# LO.net
KiCad netlist of a schematic drawn in Altium Designer
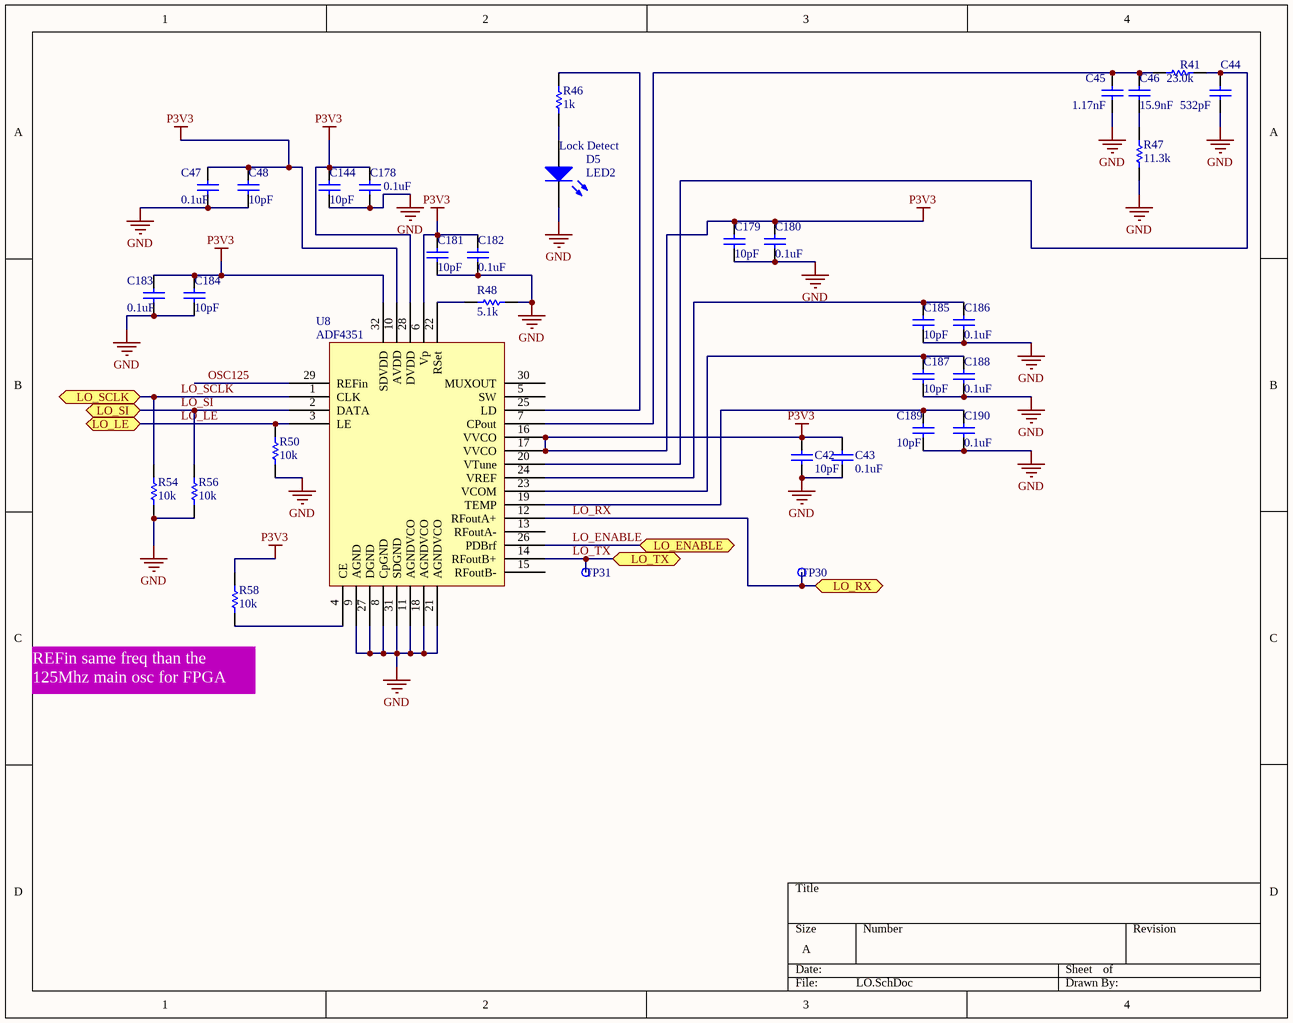
[diagram p0: LO.SchDoc]

(export (version "E")
  (design (tool "Eeschema 10.0.6"))
  (components
    (comp (ref "C42")
      (value "10pF")
      (footprint "0402")
      (description "Capacitor (Semiconductor SIM Model)")
      (fields (field (name "Comment") "Cap Semi") (field (name "PUBLISHER") "Altium Limited"))
      (libsource (lib "Miscellaneous Devices") (part "Cap Semi"))
    )
    (comp (ref "C43")
      (value "0.1uF")
      (footprint "0402")
      (description "Capacitor (Semiconductor SIM Model)")
      (fields (field (name "Comment") "Cap Semi") (field (name "PUBLISHER") "Altium Limited"))
      (libsource (lib "Miscellaneous Devices") (part "Cap Semi"))
    )
    (comp (ref "C44")
      (value "532pF")
      (footprint "0402")
      (description "Capacitor (Semiconductor SIM Model)")
      (fields (field (name "Comment") "Cap Semi") (field (name "PUBLISHER") "Altium Limited"))
      (libsource (lib "Miscellaneous Devices") (part "Cap Semi"))
    )
    (comp (ref "C45")
      (value "1.17nF")
      (footprint "0402")
      (description "Capacitor (Semiconductor SIM Model)")
      (fields (field (name "Comment") "Cap Semi") (field (name "PUBLISHER") "Altium Limited"))
      (libsource (lib "Miscellaneous Devices") (part "Cap Semi"))
    )
    (comp (ref "C46")
      (value "15.9nF")
      (footprint "0402")
      (description "Capacitor (Semiconductor SIM Model)")
      (fields (field (name "Comment") "Cap Semi") (field (name "PUBLISHER") "Altium Limited"))
      (libsource (lib "Miscellaneous Devices") (part "Cap Semi"))
    )
    (comp (ref "C47")
      (value "0.1uF")
      (footprint "0402")
      (description "Capacitor (Semiconductor SIM Model)")
      (fields (field (name "Comment") "Cap Semi") (field (name "PUBLISHER") "Altium Limited"))
      (libsource (lib "Miscellaneous Devices") (part "Cap Semi"))
    )
    (comp (ref "C48")
      (value "10pF")
      (footprint "0402")
      (description "Capacitor (Semiconductor SIM Model)")
      (fields (field (name "Comment") "Cap Semi") (field (name "PUBLISHER") "Altium Limited"))
      (libsource (lib "Miscellaneous Devices") (part "Cap Semi"))
    )
    (comp (ref "C144")
      (value "10pF")
      (footprint "0402")
      (description "Capacitor (Semiconductor SIM Model)")
      (fields (field (name "Comment") "Cap Semi") (field (name "PUBLISHER") "Altium Limited"))
      (libsource (lib "Miscellaneous Devices") (part "Cap Semi"))
    )
    (comp (ref "C178")
      (value "0.1uF")
      (footprint "0402")
      (description "Capacitor (Semiconductor SIM Model)")
      (fields (field (name "Comment") "Cap Semi") (field (name "PUBLISHER") "Altium Limited"))
      (libsource (lib "Miscellaneous Devices") (part "Cap Semi"))
    )
    (comp (ref "C179")
      (value "10pF")
      (footprint "0402")
      (description "Capacitor (Semiconductor SIM Model)")
      (fields (field (name "Comment") "Cap Semi") (field (name "PUBLISHER") "Altium Limited"))
      (libsource (lib "Miscellaneous Devices") (part "Cap Semi"))
    )
    (comp (ref "C180")
      (value "0.1uF")
      (footprint "0402")
      (description "Capacitor (Semiconductor SIM Model)")
      (fields (field (name "Comment") "Cap Semi") (field (name "PUBLISHER") "Altium Limited"))
      (libsource (lib "Miscellaneous Devices") (part "Cap Semi"))
    )
    (comp (ref "C181")
      (value "10pF")
      (footprint "0402")
      (description "Capacitor (Semiconductor SIM Model)")
      (fields (field (name "Comment") "Cap Semi") (field (name "PUBLISHER") "Altium Limited"))
      (libsource (lib "Miscellaneous Devices") (part "Cap Semi"))
    )
    (comp (ref "C182")
      (value "0.1uF")
      (footprint "0402")
      (description "Capacitor (Semiconductor SIM Model)")
      (fields (field (name "Comment") "Cap Semi") (field (name "PUBLISHER") "Altium Limited"))
      (libsource (lib "Miscellaneous Devices") (part "Cap Semi"))
    )
    (comp (ref "C183")
      (value "0.1uF")
      (footprint "0402")
      (description "Capacitor (Semiconductor SIM Model)")
      (fields (field (name "Comment") "Cap Semi") (field (name "PUBLISHER") "Altium Limited"))
      (libsource (lib "Miscellaneous Devices") (part "Cap Semi"))
    )
    (comp (ref "C184")
      (value "10pF")
      (footprint "0402")
      (description "Capacitor (Semiconductor SIM Model)")
      (fields (field (name "Comment") "Cap Semi") (field (name "PUBLISHER") "Altium Limited"))
      (libsource (lib "Miscellaneous Devices") (part "Cap Semi"))
    )
    (comp (ref "C185")
      (value "10pF")
      (footprint "0402")
      (description "Capacitor (Semiconductor SIM Model)")
      (fields (field (name "Comment") "Cap Semi") (field (name "PUBLISHER") "Altium Limited"))
      (libsource (lib "Miscellaneous Devices") (part "Cap Semi"))
    )
    (comp (ref "C186")
      (value "0.1uF")
      (footprint "0402")
      (description "Capacitor (Semiconductor SIM Model)")
      (fields (field (name "Comment") "Cap Semi") (field (name "PUBLISHER") "Altium Limited"))
      (libsource (lib "Miscellaneous Devices") (part "Cap Semi"))
    )
    (comp (ref "C187")
      (value "10pF")
      (footprint "0402")
      (description "Capacitor (Semiconductor SIM Model)")
      (fields (field (name "Comment") "Cap Semi") (field (name "PUBLISHER") "Altium Limited"))
      (libsource (lib "Miscellaneous Devices") (part "Cap Semi"))
    )
    (comp (ref "C188")
      (value "0.1uF")
      (footprint "0402")
      (description "Capacitor (Semiconductor SIM Model)")
      (fields (field (name "Comment") "Cap Semi") (field (name "PUBLISHER") "Altium Limited"))
      (libsource (lib "Miscellaneous Devices") (part "Cap Semi"))
    )
    (comp (ref "C189")
      (value "10pF")
      (footprint "0402")
      (description "Capacitor (Semiconductor SIM Model)")
      (fields (field (name "Comment") "Cap Semi") (field (name "PUBLISHER") "Altium Limited"))
      (libsource (lib "Miscellaneous Devices") (part "Cap Semi"))
    )
    (comp (ref "C190")
      (value "0.1uF")
      (footprint "0402")
      (description "Capacitor (Semiconductor SIM Model)")
      (fields (field (name "Comment") "Cap Semi") (field (name "PUBLISHER") "Altium Limited"))
      (libsource (lib "Miscellaneous Devices") (part "Cap Semi"))
    )
    (comp (ref "D5")
      (value "LED2")
      (footprint "0603")
      (description "Typical RED, GREEN, YELLOW, AMBER GaAs LED")
      (fields (field (name "PUBLISHER") "Altium Limited"))
      (libsource (lib "Miscellaneous Devices") (part "LED2"))
    )
    (comp (ref "R41")
      (value "23.0k")
      (footprint "0402")
      (description "Semiconductor Resistor")
      (fields (field (name "Comment") "Res Semi") (field (name "PUBLISHER") "Altium Limited"))
      (libsource (lib "Miscellaneous Devices") (part "Res Semi"))
    )
    (comp (ref "R46")
      (value "1k")
      (footprint "0402")
      (description "Semiconductor Resistor")
      (fields (field (name "Comment") "Res Semi") (field (name "PUBLISHER") "Altium Limited"))
      (libsource (lib "Miscellaneous Devices") (part "Res Semi"))
    )
    (comp (ref "R47")
      (value "11.3k")
      (footprint "0402")
      (description "Semiconductor Resistor")
      (fields (field (name "Comment") "Res Semi") (field (name "PUBLISHER") "Altium Limited"))
      (libsource (lib "Miscellaneous Devices") (part "Res Semi"))
    )
    (comp (ref "R48")
      (value "5.1k")
      (footprint "0402")
      (description "Semiconductor Resistor")
      (fields (field (name "Comment") "Res Semi") (field (name "PUBLISHER") "Altium Limited"))
      (libsource (lib "Miscellaneous Devices") (part "Res Semi"))
    )
    (comp (ref "R50")
      (value "10k")
      (footprint "0402")
      (description "Semiconductor Resistor")
      (fields (field (name "Comment") "Res Semi") (field (name "PUBLISHER") "Altium Limited"))
      (libsource (lib "Miscellaneous Devices") (part "Res Semi"))
    )
    (comp (ref "R54")
      (value "10k")
      (footprint "0402")
      (description "Semiconductor Resistor")
      (fields (field (name "Comment") "Res Semi") (field (name "PUBLISHER") "Altium Limited"))
      (libsource (lib "Miscellaneous Devices") (part "Res Semi"))
    )
    (comp (ref "R56")
      (value "10k")
      (footprint "0402")
      (description "Semiconductor Resistor")
      (fields (field (name "Comment") "Res Semi") (field (name "PUBLISHER") "Altium Limited"))
      (libsource (lib "Miscellaneous Devices") (part "Res Semi"))
    )
    (comp (ref "R58")
      (value "10k")
      (footprint "0402")
      (description "Semiconductor Resistor")
      (fields (field (name "Comment") "Res Semi") (field (name "PUBLISHER") "Altium Limited"))
      (libsource (lib "Miscellaneous Devices") (part "Res Semi"))
    )
    (comp (ref "TP30")
      (value "LO_RX")
      (footprint "TPS127")
      (description "Test Point")
      (fields (field (name "PART NUMBER") "SMD_PAD_1.27X1.27MM") (field (name "AUTHOR") "CERN DEM JLC"))
      (libsource (lib "Eletro-mechanical") (part "Test Point"))
    )
    (comp (ref "TP31")
      (value "LO_TX")
      (footprint "TPS127")
      (description "Test Point")
      (fields (field (name "PART NUMBER") "SMD_PAD_1.27X1.27MM") (field (name "AUTHOR") "CERN DEM JLC"))
      (libsource (lib "Eletro-mechanical") (part "Test Point"))
    )
    (comp (ref "U8")
      (value "ADF4351")
      (footprint "ADF4350_QFN32")
      (description "VCO")
      (libsource (lib "shield_components") (part "ADF4350"))
    )
  )
  (nets
    (net (code "1") (name "/LO_ENABLE") (class "Default")
      (node (ref "U8") (pin "26") (pinfunction "PDBrf_26") (pintype "passive"))
    )
    (net (code "2") (name "/LO_LE") (class "Default")
      (node (ref "R50") (pin "1") (pinfunction "1_1") (pintype "passive"))
      (node (ref "U8") (pin "3") (pinfunction "LE_3") (pintype "passive"))
    )
    (net (code "3") (name "/LO_RX") (class "Default")
      (node (ref "TP30") (pin "1") (pinfunction "1_1") (pintype "bidirectional"))
      (node (ref "U8") (pin "12") (pinfunction "RFoutA+_12") (pintype "passive"))
    )
    (net (code "4") (name "/LO_SCLK") (class "Default")
      (node (ref "R54") (pin "1") (pinfunction "1_1") (pintype "passive"))
      (node (ref "U8") (pin "1") (pinfunction "CLK_1") (pintype "passive"))
    )
    (net (code "5") (name "/LO_SI") (class "Default")
      (node (ref "R56") (pin "1") (pinfunction "1_1") (pintype "passive"))
      (node (ref "U8") (pin "2") (pinfunction "DATA_2") (pintype "passive"))
    )
    (net (code "6") (name "/LO_TX") (class "Default")
      (node (ref "TP31") (pin "1") (pinfunction "1_1") (pintype "bidirectional"))
      (node (ref "U8") (pin "14") (pinfunction "RFoutB+_14") (pintype "passive"))
    )
    (net (code "7") (name "/OSC125") (class "Default")
      (node (ref "U8") (pin "29") (pinfunction "REFin_29") (pintype "passive"))
    )
    (net (code "8") (name "GND") (class "Default")
      (node (ref "C144") (pin "2") (pinfunction "2_2") (pintype "passive"))
      (node (ref "C178") (pin "2") (pinfunction "2_2") (pintype "passive"))
      (node (ref "C179") (pin "2") (pinfunction "2_2") (pintype "passive"))
      (node (ref "C180") (pin "2") (pinfunction "2_2") (pintype "passive"))
      (node (ref "C181") (pin "2") (pinfunction "2_2") (pintype "passive"))
      (node (ref "C182") (pin "2") (pinfunction "2_2") (pintype "passive"))
      (node (ref "C183") (pin "2") (pinfunction "2_2") (pintype "passive"))
      (node (ref "C184") (pin "2") (pinfunction "2_2") (pintype "passive"))
      (node (ref "C185") (pin "2") (pinfunction "2_2") (pintype "passive"))
      (node (ref "C186") (pin "2") (pinfunction "2_2") (pintype "passive"))
      (node (ref "C187") (pin "2") (pinfunction "2_2") (pintype "passive"))
      (node (ref "C188") (pin "2") (pinfunction "2_2") (pintype "passive"))
      (node (ref "C189") (pin "2") (pinfunction "2_2") (pintype "passive"))
      (node (ref "C190") (pin "2") (pinfunction "2_2") (pintype "passive"))
      (node (ref "C42") (pin "2") (pinfunction "2_2") (pintype "passive"))
      (node (ref "C43") (pin "2") (pinfunction "2_2") (pintype "passive"))
      (node (ref "C44") (pin "2") (pinfunction "2_2") (pintype "passive"))
      (node (ref "C45") (pin "2") (pinfunction "2_2") (pintype "passive"))
      (node (ref "C47") (pin "2") (pinfunction "2_2") (pintype "passive"))
      (node (ref "C48") (pin "2") (pinfunction "2_2") (pintype "passive"))
      (node (ref "D5") (pin "2") (pinfunction "K_2") (pintype "passive"))
      (node (ref "R47") (pin "2") (pinfunction "2_2") (pintype "passive"))
      (node (ref "R48") (pin "1") (pinfunction "1_1") (pintype "passive"))
      (node (ref "R50") (pin "2") (pinfunction "2_2") (pintype "passive"))
      (node (ref "R54") (pin "2") (pinfunction "2_2") (pintype "passive"))
      (node (ref "R56") (pin "2") (pinfunction "2_2") (pintype "passive"))
      (node (ref "U8") (pin "11") (pinfunction "AGNDVCO_11") (pintype "power_in"))
      (node (ref "U8") (pin "18") (pinfunction "AGNDVCO_18") (pintype "power_in"))
      (node (ref "U8") (pin "21") (pinfunction "AGNDVCO_21") (pintype "power_in"))
      (node (ref "U8") (pin "27") (pinfunction "DGND_27") (pintype "power_in"))
      (node (ref "U8") (pin "31") (pinfunction "SDGND_31") (pintype "power_in"))
      (node (ref "U8") (pin "8") (pinfunction "CpGND_8") (pintype "power_in"))
      (node (ref "U8") (pin "9") (pinfunction "AGND_9") (pintype "power_in"))
    )
    (net (code "9") (name "Net-(C46-Pad2)") (class "Default")
      (node (ref "C46") (pin "2") (pinfunction "2_2") (pintype "passive"))
      (node (ref "R47") (pin "1") (pinfunction "1_1") (pintype "passive"))
    )
    (net (code "10") (name "Net-(D5-A)") (class "Default")
      (node (ref "D5") (pin "1") (pinfunction "A_1") (pintype "passive"))
      (node (ref "R46") (pin "2") (pinfunction "2_2") (pintype "passive"))
    )
    (net (code "11") (name "Net-(U8-CE)") (class "Default")
      (node (ref "R58") (pin "2") (pinfunction "2_2") (pintype "passive"))
      (node (ref "U8") (pin "4") (pinfunction "CE_4") (pintype "passive"))
    )
    (net (code "12") (name "Net-(U8-CPout)") (class "Default")
      (node (ref "C45") (pin "1") (pinfunction "1_1") (pintype "passive"))
      (node (ref "C46") (pin "1") (pinfunction "1_1") (pintype "passive"))
      (node (ref "R41") (pin "2") (pinfunction "2_2") (pintype "passive"))
      (node (ref "U8") (pin "7") (pinfunction "CPout_7") (pintype "passive"))
    )
    (net (code "13") (name "Net-(U8-LD)") (class "Default")
      (node (ref "R46") (pin "1") (pinfunction "1_1") (pintype "passive"))
      (node (ref "U8") (pin "25") (pinfunction "LD_25") (pintype "passive"))
    )
    (net (code "14") (name "Net-(U8-RSet)") (class "Default")
      (node (ref "R48") (pin "2") (pinfunction "2_2") (pintype "passive"))
      (node (ref "U8") (pin "22") (pinfunction "RSet_22") (pintype "passive"))
    )
    (net (code "15") (name "Net-(U8-TEMP)") (class "Default")
      (node (ref "C189") (pin "1") (pinfunction "1_1") (pintype "passive"))
      (node (ref "C190") (pin "1") (pinfunction "1_1") (pintype "passive"))
      (node (ref "U8") (pin "19") (pinfunction "TEMP_19") (pintype "passive"))
    )
    (net (code "16") (name "Net-(U8-VCOM)") (class "Default")
      (node (ref "C187") (pin "1") (pinfunction "1_1") (pintype "passive"))
      (node (ref "C188") (pin "1") (pinfunction "1_1") (pintype "passive"))
      (node (ref "U8") (pin "23") (pinfunction "VCOM_23") (pintype "power_in"))
    )
    (net (code "17") (name "Net-(U8-VREF)") (class "Default")
      (node (ref "C185") (pin "1") (pinfunction "1_1") (pintype "passive"))
      (node (ref "C186") (pin "1") (pinfunction "1_1") (pintype "passive"))
      (node (ref "U8") (pin "24") (pinfunction "VREF_24") (pintype "power_in"))
    )
    (net (code "18") (name "Net-(U8-VTune)") (class "Default")
      (node (ref "C44") (pin "1") (pinfunction "1_1") (pintype "passive"))
      (node (ref "R41") (pin "1") (pinfunction "1_1") (pintype "passive"))
      (node (ref "U8") (pin "20") (pinfunction "VTune_20") (pintype "passive"))
    )
    (net (code "19") (name "P3V3") (class "Default")
      (node (ref "C144") (pin "1") (pinfunction "1_1") (pintype "passive"))
      (node (ref "C178") (pin "1") (pinfunction "1_1") (pintype "passive"))
      (node (ref "C179") (pin "1") (pinfunction "1_1") (pintype "passive"))
      (node (ref "C180") (pin "1") (pinfunction "1_1") (pintype "passive"))
      (node (ref "C181") (pin "1") (pinfunction "1_1") (pintype "passive"))
      (node (ref "C182") (pin "1") (pinfunction "1_1") (pintype "passive"))
      (node (ref "C183") (pin "1") (pinfunction "1_1") (pintype "passive"))
      (node (ref "C184") (pin "1") (pinfunction "1_1") (pintype "passive"))
      (node (ref "C42") (pin "1") (pinfunction "1_1") (pintype "passive"))
      (node (ref "C43") (pin "1") (pinfunction "1_1") (pintype "passive"))
      (node (ref "C47") (pin "1") (pinfunction "1_1") (pintype "passive"))
      (node (ref "C48") (pin "1") (pinfunction "1_1") (pintype "passive"))
      (node (ref "R58") (pin "1") (pinfunction "1_1") (pintype "passive"))
      (node (ref "U8") (pin "10") (pinfunction "AVDD_10") (pintype "power_in"))
      (node (ref "U8") (pin "16") (pinfunction "VVCO_16") (pintype "power_in"))
      (node (ref "U8") (pin "17") (pinfunction "VVCO_17") (pintype "power_in"))
      (node (ref "U8") (pin "28") (pinfunction "DVDD_28") (pintype "power_in"))
      (node (ref "U8") (pin "32") (pinfunction "SDVDD_32") (pintype "power_in"))
      (node (ref "U8") (pin "6") (pinfunction "Vp_6") (pintype "power_in"))
    )
    (net (code "20") (name "unconnected-(U8-MUXOUT-Pad30)") (class "Default")
      (node (ref "U8") (pin "30") (pinfunction "MUXOUT_30") (pintype "passive"))
    )
    (net (code "21") (name "unconnected-(U8-RFoutA--Pad13)") (class "Default")
      (node (ref "U8") (pin "13") (pinfunction "RFoutA-_13") (pintype "passive"))
    )
    (net (code "22") (name "unconnected-(U8-RFoutB--Pad15)") (class "Default")
      (node (ref "U8") (pin "15") (pinfunction "RFoutB-_15") (pintype "passive"))
    )
    (net (code "23") (name "unconnected-(U8-SW-Pad5)") (class "Default")
      (node (ref "U8") (pin "5") (pinfunction "SW_5") (pintype "passive"))
    )
  )
)
